# haystack_rgb_single_wires.net
KiCad netlist of a schematic drawn in EAGLE
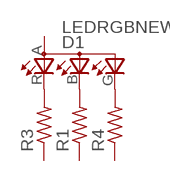
[diagram p0: schematic, sheet 1]

(export (version "E")
  (design (tool "Eeschema 10.0.6"))
  (components
    (comp (ref "D1")
      (value "LEDRGBNEW")
      (footprint "eagle-import:P-LCC-4")
      (libsource (lib "eagle-import") (part "LEDRGBNEW"))
    )
    (comp (ref "R1")
      (value "RES-US1206")
      (footprint "eagle-import:R1206")
      (libsource (lib "eagle-import") (part "RES-US1206"))
    )
    (comp (ref "R3")
      (value "RES-US1206")
      (footprint "eagle-import:R1206")
      (libsource (lib "eagle-import") (part "RES-US1206"))
    )
    (comp (ref "R4")
      (value "RES-US1206")
      (footprint "eagle-import:R1206")
      (libsource (lib "eagle-import") (part "RES-US1206"))
    )
  )
  (nets
    (net (code "1") (name "Net-(D1-CBLUE)") (class "Default")
      (node (ref "D1") (pin "B") (pinfunction "CBLUE_B") (pintype "passive"))
      (node (ref "R1") (pin "2") (pinfunction "2_2") (pintype "passive"))
    )
    (net (code "2") (name "Net-(D1-CGREEN)") (class "Default")
      (node (ref "D1") (pin "G") (pinfunction "CGREEN_G") (pintype "passive"))
      (node (ref "R4") (pin "2") (pinfunction "2_2") (pintype "passive"))
    )
    (net (code "3") (name "Net-(D1-CRED)") (class "Default")
      (node (ref "D1") (pin "R") (pinfunction "CRED_R") (pintype "passive"))
      (node (ref "R3") (pin "2") (pinfunction "2_2") (pintype "passive"))
    )
    (net (code "4") (name "unconnected-(D1-A2-PadA)") (class "Default")
      (node (ref "D1") (pin "A") (pinfunction "A2_A") (pintype "passive"))
    )
    (net (code "5") (name "unconnected-(R1-Pad1)") (class "Default")
      (node (ref "R1") (pin "1") (pinfunction "1_1") (pintype "passive"))
    )
    (net (code "6") (name "unconnected-(R3-Pad1)") (class "Default")
      (node (ref "R3") (pin "1") (pinfunction "1_1") (pintype "passive"))
    )
    (net (code "7") (name "unconnected-(R4-Pad1)") (class "Default")
      (node (ref "R4") (pin "1") (pinfunction "1_1") (pintype "passive"))
    )
  )
)
